# esp8266_lua_test.net
KiCad netlist of a schematic drawn in EAGLE
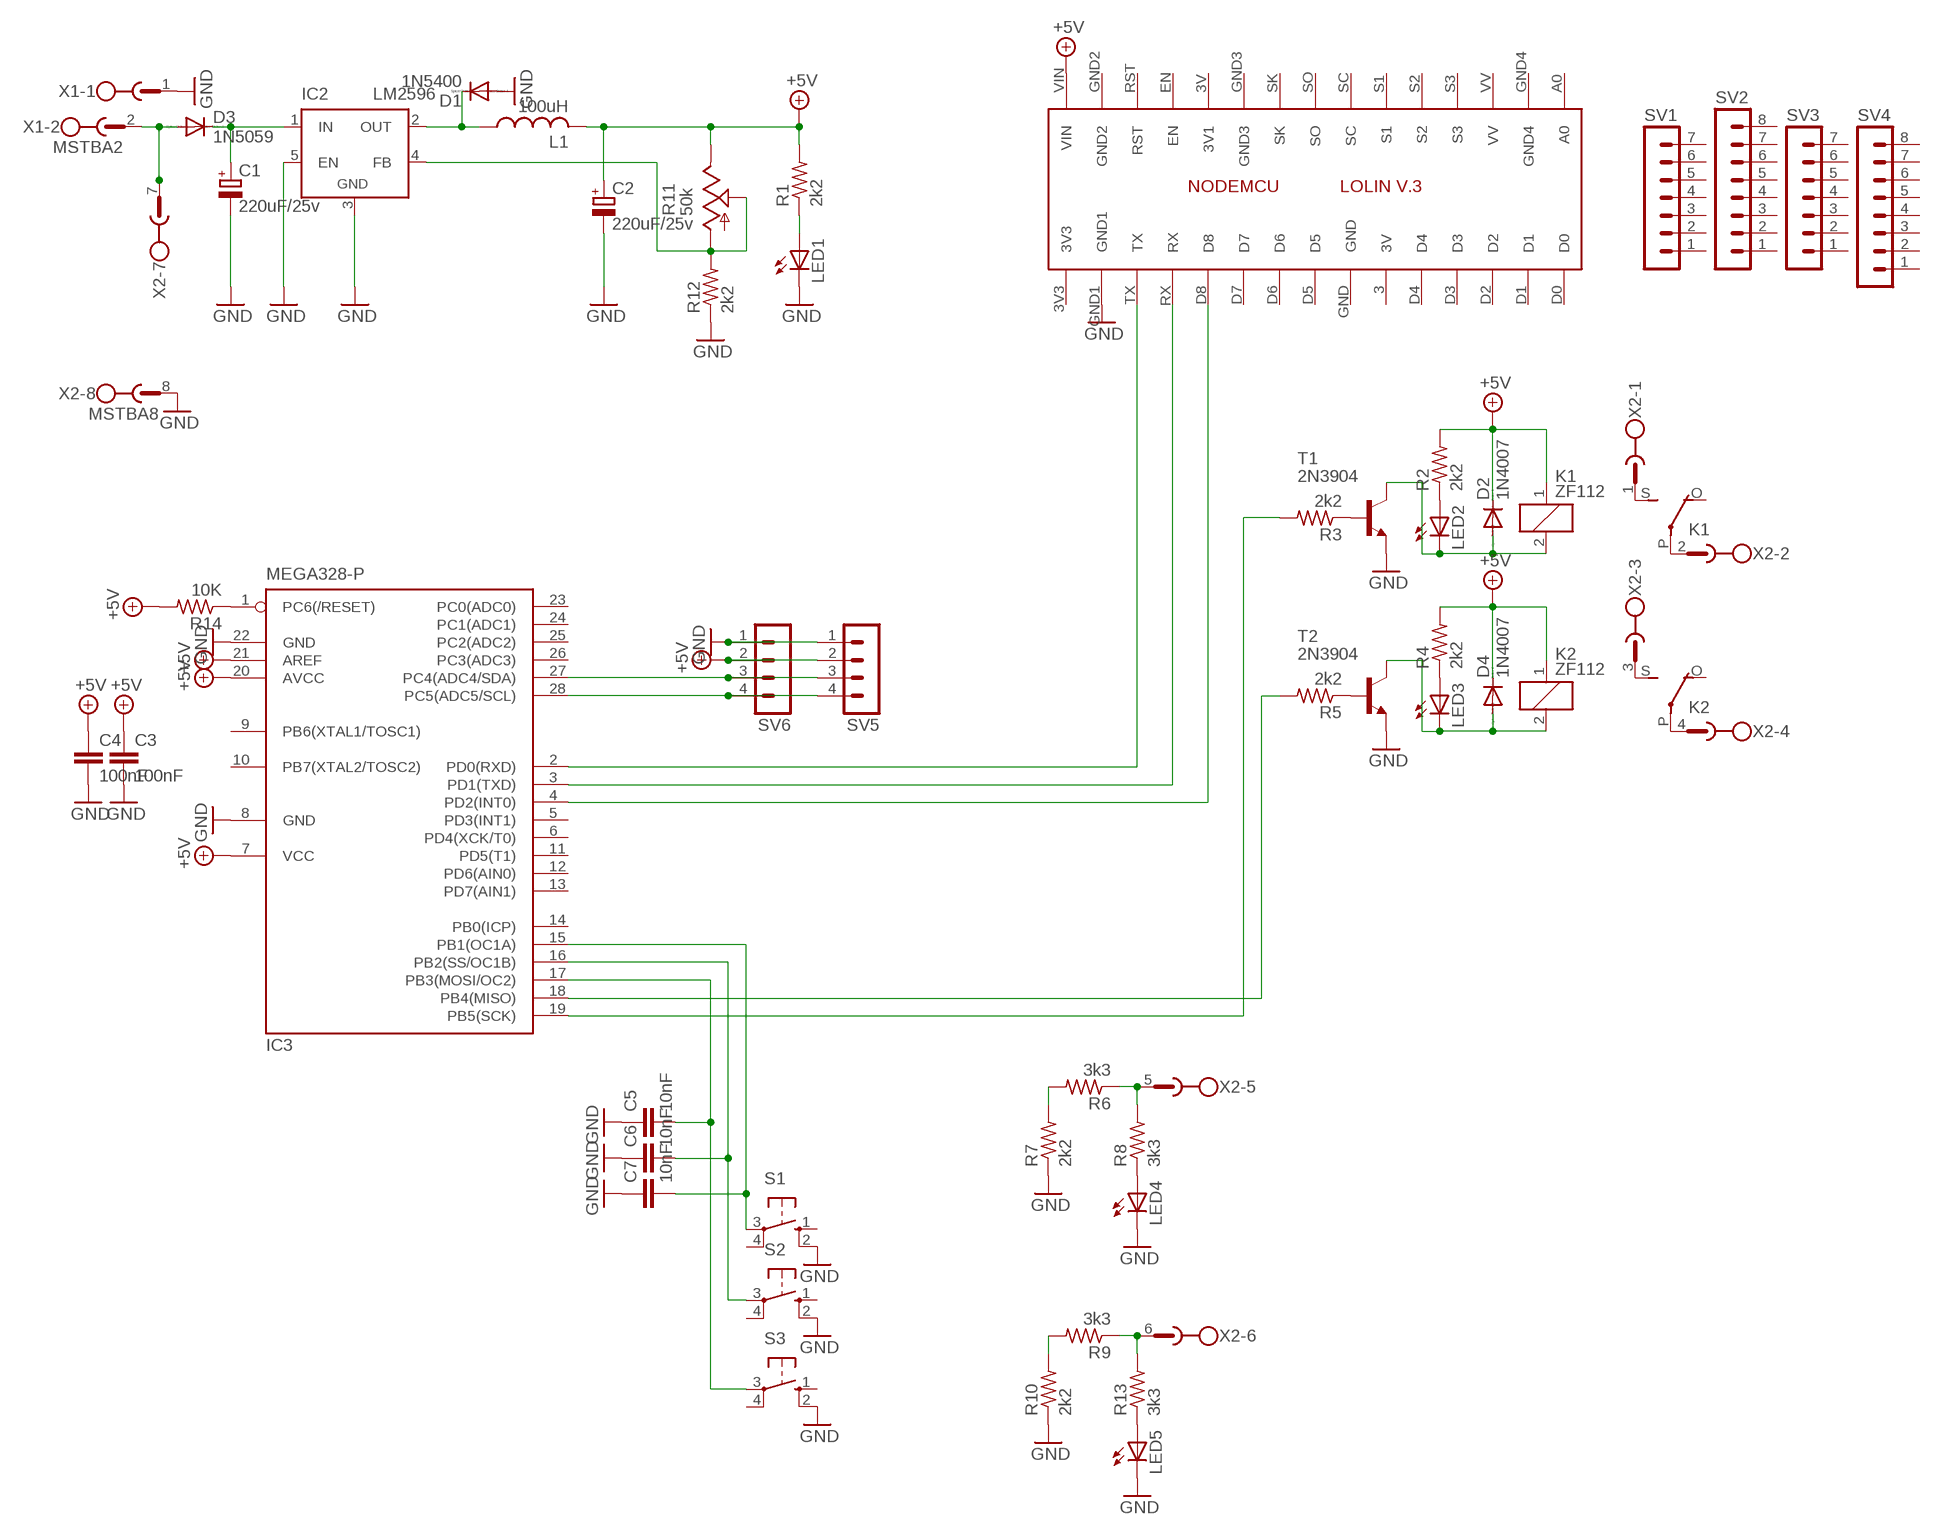
[diagram p0: schematic, sheet 1]

(export (version "E")
  (design (tool "Eeschema 10.0.6"))
  (components
    (comp (ref "C1")
      (value "220uF/25v")
      (footprint "eagle-import:E3,5-10")
      (libsource (lib "eagle-import") (part "CPOL-EUE3.5-10"))
    )
    (comp (ref "C2")
      (value "220uF/25v")
      (footprint "eagle-import:E3,5-10")
      (libsource (lib "eagle-import") (part "CPOL-EUE3.5-10"))
    )
    (comp (ref "C3")
      (value "100nF")
      (footprint "eagle-import:C050-024X044")
      (libsource (lib "eagle-import") (part "C-EU050-024X044"))
    )
    (comp (ref "C4")
      (value "100nF")
      (footprint "eagle-import:C050-024X044")
      (libsource (lib "eagle-import") (part "C-EU050-024X044"))
    )
    (comp (ref "C5")
      (value "10nF")
      (footprint "eagle-import:C050-024X044")
      (libsource (lib "eagle-import") (part "C-EU050-024X044"))
    )
    (comp (ref "C6")
      (value "10nF")
      (footprint "eagle-import:C050-024X044")
      (libsource (lib "eagle-import") (part "C-EU050-024X044"))
    )
    (comp (ref "C7")
      (value "10nF")
      (footprint "eagle-import:C050-024X044")
      (libsource (lib "eagle-import") (part "C-EU050-024X044"))
    )
    (comp (ref "D1")
      (value "1N5400")
      (footprint "eagle-import:DO201-15")
      (libsource (lib "eagle-import") (part "1N5400"))
    )
    (comp (ref "D2")
      (value "1N4007")
      (footprint "eagle-import:DO35-7")
      (libsource (lib "eagle-import") (part "1N4148DO35-7"))
    )
    (comp (ref "D3")
      (value "1N5059")
      (footprint "eagle-import:DO204-10")
      (libsource (lib "eagle-import") (part "1N5059"))
    )
    (comp (ref "D4")
      (value "1N4007")
      (footprint "eagle-import:DO35-7")
      (libsource (lib "eagle-import") (part "1N4148DO35-7"))
    )
    (comp (ref "IC1")
      (value "LOLINV3")
      (footprint "eagle-import:LOLINV3")
      (libsource (lib "eagle-import") (part "LOLINV3"))
    )
    (comp (ref "IC2")
      (value "LM2596")
      (footprint "eagle-import:TO220-51")
      (libsource (lib "eagle-import") (part "LM2596TV"))
    )
    (comp (ref "IC3")
      (value "MEGA328-P")
      (footprint "eagle-import:DIL28-3")
      (libsource (lib "eagle-import") (part "MEGA8-P"))
    )
    (comp (ref "K1")
      (value "ZF112")
      (footprint "eagle-import:ZF112")
      (libsource (lib "eagle-import") (part "ZF112"))
    )
    (comp (ref "K2")
      (value "ZF112")
      (footprint "eagle-import:ZF112")
      (libsource (lib "eagle-import") (part "ZF112"))
    )
    (comp (ref "L1")
      (value "100uH")
      (footprint "eagle-import:6000-XXXX-RC")
      (libsource (lib "eagle-import") (part "L-US6000-XXX-RC"))
    )
    (comp (ref "LED1")
      (value "LED3MM")
      (footprint "eagle-import:LED3MM")
      (libsource (lib "eagle-import") (part "LED3MM"))
    )
    (comp (ref "LED2")
      (value "LED3MM")
      (footprint "eagle-import:LED3MM")
      (libsource (lib "eagle-import") (part "LED3MM"))
    )
    (comp (ref "LED3")
      (value "LED3MM")
      (footprint "eagle-import:LED3MM")
      (libsource (lib "eagle-import") (part "LED3MM"))
    )
    (comp (ref "LED4")
      (value "LED3MM")
      (footprint "eagle-import:LED3MM")
      (libsource (lib "eagle-import") (part "LED3MM"))
    )
    (comp (ref "LED5")
      (value "LED3MM")
      (footprint "eagle-import:LED3MM")
      (libsource (lib "eagle-import") (part "LED3MM"))
    )
    (comp (ref "R1")
      (value "2k2")
      (footprint "eagle-import:0207_10")
      (libsource (lib "eagle-import") (part "R-US_0207/10"))
    )
    (comp (ref "R2")
      (value "2k2")
      (footprint "eagle-import:0207_10")
      (libsource (lib "eagle-import") (part "R-US_0207/10"))
    )
    (comp (ref "R3")
      (value "2k2")
      (footprint "eagle-import:0207_10")
      (libsource (lib "eagle-import") (part "R-US_0207/10"))
    )
    (comp (ref "R4")
      (value "2k2")
      (footprint "eagle-import:0207_10")
      (libsource (lib "eagle-import") (part "R-US_0207/10"))
    )
    (comp (ref "R5")
      (value "2k2")
      (footprint "eagle-import:0207_10")
      (libsource (lib "eagle-import") (part "R-US_0207/10"))
    )
    (comp (ref "R6")
      (value "3k3")
      (footprint "eagle-import:0207_10")
      (libsource (lib "eagle-import") (part "R-US_0207/10"))
    )
    (comp (ref "R7")
      (value "2k2")
      (footprint "eagle-import:0207_10")
      (libsource (lib "eagle-import") (part "R-US_0207/10"))
    )
    (comp (ref "R8")
      (value "3k3")
      (footprint "eagle-import:0207_10")
      (libsource (lib "eagle-import") (part "R-US_0207/10"))
    )
    (comp (ref "R9")
      (value "3k3")
      (footprint "eagle-import:0207_10")
      (libsource (lib "eagle-import") (part "R-US_0207/10"))
    )
    (comp (ref "R10")
      (value "2k2")
      (footprint "eagle-import:0207_10")
      (libsource (lib "eagle-import") (part "R-US_0207/10"))
    )
    (comp (ref "R11")
      (value "50k")
      (footprint "eagle-import:B25P")
      (libsource (lib "eagle-import") (part "TRIM_US-B25P"))
    )
    (comp (ref "R12")
      (value "2k2")
      (footprint "eagle-import:0207_10")
      (libsource (lib "eagle-import") (part "R-US_0207/10"))
    )
    (comp (ref "R13")
      (value "3k3")
      (footprint "eagle-import:0207_10")
      (libsource (lib "eagle-import") (part "R-US_0207/10"))
    )
    (comp (ref "R14")
      (value "10K")
      (footprint "eagle-import:0207_10")
      (libsource (lib "eagle-import") (part "R-US_0207/10"))
    )
    (comp (ref "S1")
      (value "10-XX")
      (footprint "eagle-import:B3F-10XX")
      (fields (field (name "MPN") "B3F-1000"))
      (libsource (lib "eagle-import") (part "10-XX"))
    )
    (comp (ref "S2")
      (value "10-XX")
      (footprint "eagle-import:B3F-10XX")
      (fields (field (name "MPN") "B3F-1000"))
      (libsource (lib "eagle-import") (part "10-XX"))
    )
    (comp (ref "S3")
      (value "10-XX")
      (footprint "eagle-import:B3F-10XX")
      (fields (field (name "MPN") "B3F-1000"))
      (libsource (lib "eagle-import") (part "10-XX"))
    )
    (comp (ref "SV1")
      (value "MA07-1")
      (footprint "eagle-import:MA07-1")
      (libsource (lib "eagle-import") (part "MA07-1"))
    )
    (comp (ref "SV2")
      (value "MA08-1")
      (footprint "eagle-import:MA08-1")
      (libsource (lib "eagle-import") (part "MA08-1"))
    )
    (comp (ref "SV3")
      (value "MA07-1")
      (footprint "eagle-import:MA07-1")
      (libsource (lib "eagle-import") (part "MA07-1"))
    )
    (comp (ref "SV4")
      (value "MA08-1")
      (footprint "eagle-import:MA08-1")
      (libsource (lib "eagle-import") (part "MA08-1"))
    )
    (comp (ref "SV5")
      (value "MA04-1")
      (footprint "eagle-import:MA04-1")
      (libsource (lib "eagle-import") (part "MA04-1"))
    )
    (comp (ref "SV6")
      (value "MA04-1")
      (footprint "eagle-import:MA04-1")
      (libsource (lib "eagle-import") (part "MA04-1"))
    )
    (comp (ref "T1")
      (value "2N3904")
      (footprint "eagle-import:TO92-EBC")
      (libsource (lib "eagle-import") (part "-NPN-TO92-EBC2N3904"))
    )
    (comp (ref "T2")
      (value "2N3904")
      (footprint "eagle-import:TO92-EBC")
      (libsource (lib "eagle-import") (part "-NPN-TO92-EBC2N3904"))
    )
    (comp (ref "X1")
      (value "MSTBA2")
      (footprint "eagle-import:MSTBA2")
      (fields (field (name "MF") "FARNELL") (field (name "MPN") "1757242"))
      (libsource (lib "eagle-import") (part "MSTBA2"))
    )
    (comp (ref "X2")
      (value "MSTBA8")
      (footprint "eagle-import:MSTBA8")
      (fields (field (name "MF") "FARNELL") (field (name "MPN") "1757307"))
      (libsource (lib "eagle-import") (part "MSTBA8"))
    )
  )
  (nets
    (net (code "1") (name "+5V") (class "Default")
      (node (ref "C2") (pin "+") (pinfunction "+_+") (pintype "passive"))
      (node (ref "C3") (pin "1") (pinfunction "1_1") (pintype "passive"))
      (node (ref "C4") (pin "1") (pinfunction "1_1") (pintype "passive"))
      (node (ref "D2") (pin "C") (pinfunction "C_C") (pintype "passive"))
      (node (ref "D4") (pin "C") (pinfunction "C_C") (pintype "passive"))
      (node (ref "IC1") (pin "VIN") (pinfunction "VIN_VIN") (pintype "bidirectional"))
      (node (ref "IC3") (pin "20") (pinfunction "AVCC_20") (pintype "power_in"))
      (node (ref "IC3") (pin "21") (pinfunction "AREF_21") (pintype "passive"))
      (node (ref "IC3") (pin "7") (pinfunction "VCC_7") (pintype "power_in"))
      (node (ref "K1") (pin "1") (pinfunction "1_1") (pintype "passive"))
      (node (ref "K2") (pin "1") (pinfunction "1_1") (pintype "passive"))
      (node (ref "L1") (pin "2") (pinfunction "2_2") (pintype "passive"))
      (node (ref "R1") (pin "2") (pinfunction "2_2") (pintype "passive"))
      (node (ref "R11") (pin "E") (pinfunction "E_E") (pintype "passive"))
      (node (ref "R14") (pin "2") (pinfunction "2_2") (pintype "passive"))
      (node (ref "R2") (pin "2") (pinfunction "2_2") (pintype "passive"))
      (node (ref "R4") (pin "2") (pinfunction "2_2") (pintype "passive"))
      (node (ref "SV5") (pin "2") (pinfunction "2_2") (pintype "passive"))
      (node (ref "SV6") (pin "2") (pinfunction "2_2") (pintype "passive"))
    )
    (net (code "2") (name "GND") (class "Default")
      (node (ref "C1") (pin "-") (pinfunction "-_-") (pintype "passive"))
      (node (ref "C2") (pin "-") (pinfunction "-_-") (pintype "passive"))
      (node (ref "C3") (pin "2") (pinfunction "2_2") (pintype "passive"))
      (node (ref "C4") (pin "2") (pinfunction "2_2") (pintype "passive"))
      (node (ref "C5") (pin "1") (pinfunction "1_1") (pintype "passive"))
      (node (ref "C6") (pin "1") (pinfunction "1_1") (pintype "passive"))
      (node (ref "C7") (pin "1") (pinfunction "1_1") (pintype "passive"))
      (node (ref "D1") (pin "A") (pinfunction "A_A") (pintype "passive"))
      (node (ref "IC1") (pin "GND1") (pinfunction "GND1_GND1") (pintype "bidirectional"))
      (node (ref "IC2") (pin "3") (pinfunction "GND_3") (pintype "power_in"))
      (node (ref "IC2") (pin "5") (pinfunction "EN_5") (pintype "input"))
      (node (ref "IC3") (pin "22") (pinfunction "GND_22") (pintype "power_in"))
      (node (ref "IC3") (pin "8") (pinfunction "GND_8") (pintype "power_in"))
      (node (ref "LED1") (pin "K") (pinfunction "C_K") (pintype "passive"))
      (node (ref "LED4") (pin "K") (pinfunction "C_K") (pintype "passive"))
      (node (ref "LED5") (pin "K") (pinfunction "C_K") (pintype "passive"))
      (node (ref "R10") (pin "1") (pinfunction "1_1") (pintype "passive"))
      (node (ref "R12") (pin "1") (pinfunction "1_1") (pintype "passive"))
      (node (ref "R7") (pin "1") (pinfunction "1_1") (pintype "passive"))
      (node (ref "S1") (pin "2") (pinfunction "S1_2") (pintype "passive"))
      (node (ref "S2") (pin "2") (pinfunction "S1_2") (pintype "passive"))
      (node (ref "S3") (pin "2") (pinfunction "S1_2") (pintype "passive"))
      (node (ref "SV5") (pin "1") (pinfunction "1_1") (pintype "passive"))
      (node (ref "SV6") (pin "1") (pinfunction "1_1") (pintype "passive"))
      (node (ref "T1") (pin "E") (pinfunction "E_E") (pintype "passive"))
      (node (ref "T2") (pin "E") (pinfunction "E_E") (pintype "passive"))
      (node (ref "X1") (pin "1") (pinfunction "1_1") (pintype "passive"))
      (node (ref "X2") (pin "8") (pinfunction "1_8") (pintype "passive"))
    )
    (net (code "3") (name "Net-(IC2-FB)") (class "Default")
      (node (ref "IC2") (pin "4") (pinfunction "FB_4") (pintype "input"))
      (node (ref "R11") (pin "A") (pinfunction "A_A") (pintype "passive"))
      (node (ref "R11") (pin "S") (pinfunction "S_S") (pintype "passive"))
      (node (ref "R12") (pin "2") (pinfunction "2_2") (pintype "passive"))
    )
    (net (code "4") (name "Net-(IC2-IN)") (class "Default")
      (node (ref "C1") (pin "+") (pinfunction "+_+") (pintype "passive"))
      (node (ref "D3") (pin "C") (pinfunction "C_C") (pintype "passive"))
      (node (ref "IC2") (pin "1") (pinfunction "IN_1") (pintype "input"))
    )
    (net (code "5") (name "Net-(IC2-OUT)") (class "Default")
      (node (ref "D1") (pin "C") (pinfunction "C_C") (pintype "passive"))
      (node (ref "IC2") (pin "2") (pinfunction "OUT_2") (pintype "output"))
      (node (ref "L1") (pin "1") (pinfunction "1_1") (pintype "passive"))
    )
    (net (code "6") (name "Net-(IC3-PB1(OC1A))") (class "Default")
      (node (ref "C7") (pin "2") (pinfunction "2_2") (pintype "passive"))
      (node (ref "IC3") (pin "15") (pinfunction "PB1(OC1A)_15") (pintype "bidirectional"))
      (node (ref "S1") (pin "3") (pinfunction "P_3") (pintype "passive"))
    )
    (net (code "7") (name "Net-(IC3-PB2(SS{slash}OC1B))") (class "Default")
      (node (ref "C6") (pin "2") (pinfunction "2_2") (pintype "passive"))
      (node (ref "IC3") (pin "16") (pinfunction "PB2(SS/OC1B)_16") (pintype "bidirectional"))
      (node (ref "S2") (pin "3") (pinfunction "P_3") (pintype "passive"))
    )
    (net (code "8") (name "Net-(IC3-PB3(MOSI{slash}OC2))") (class "Default")
      (node (ref "C5") (pin "2") (pinfunction "2_2") (pintype "passive"))
      (node (ref "IC3") (pin "17") (pinfunction "PB3(MOSI/OC2)_17") (pintype "bidirectional"))
      (node (ref "S3") (pin "3") (pinfunction "P_3") (pintype "passive"))
    )
    (net (code "9") (name "Net-(IC3-PB4(MISO))") (class "Default")
      (node (ref "IC3") (pin "18") (pinfunction "PB4(MISO)_18") (pintype "bidirectional"))
      (node (ref "R5") (pin "2") (pinfunction "2_2") (pintype "passive"))
    )
    (net (code "10") (name "Net-(IC3-PB5(SCK))") (class "Default")
      (node (ref "IC3") (pin "19") (pinfunction "PB5(SCK)_19") (pintype "bidirectional"))
      (node (ref "R3") (pin "2") (pinfunction "2_2") (pintype "passive"))
    )
    (net (code "11") (name "Net-(IC3-PC4(ADC4{slash}SDA))") (class "Default")
      (node (ref "IC3") (pin "27") (pinfunction "PC4(ADC4/SDA)_27") (pintype "bidirectional"))
      (node (ref "SV5") (pin "3") (pinfunction "3_3") (pintype "passive"))
      (node (ref "SV6") (pin "3") (pinfunction "3_3") (pintype "passive"))
    )
    (net (code "12") (name "Net-(IC3-PC5(ADC5{slash}SCL))") (class "Default")
      (node (ref "IC3") (pin "28") (pinfunction "PC5(ADC5/SCL)_28") (pintype "bidirectional"))
      (node (ref "SV5") (pin "4") (pinfunction "4_4") (pintype "passive"))
      (node (ref "SV6") (pin "4") (pinfunction "4_4") (pintype "passive"))
    )
    (net (code "13") (name "Net-(IC3-PC6({slash}RESET))") (class "Default")
      (node (ref "IC3") (pin "1") (pinfunction "PC6(/RESET)_1") (pintype "bidirectional"))
      (node (ref "R14") (pin "1") (pinfunction "1_1") (pintype "passive"))
    )
    (net (code "14") (name "Net-(IC3-PD0(RXD))") (class "Default")
      (node (ref "IC1") (pin "TX") (pinfunction "TX_TX") (pintype "bidirectional"))
      (node (ref "IC3") (pin "2") (pinfunction "PD0(RXD)_2") (pintype "bidirectional"))
    )
    (net (code "15") (name "Net-(IC3-PD1(TXD))") (class "Default")
      (node (ref "IC1") (pin "RX") (pinfunction "RX_RX") (pintype "bidirectional"))
      (node (ref "IC3") (pin "3") (pinfunction "PD1(TXD)_3") (pintype "bidirectional"))
    )
    (net (code "16") (name "Net-(IC3-PD2(INT0))") (class "Default")
      (node (ref "IC1") (pin "D8") (pinfunction "D8_D8") (pintype "bidirectional"))
      (node (ref "IC3") (pin "4") (pinfunction "PD2(INT0)_4") (pintype "bidirectional"))
    )
    (net (code "17") (name "Net-(K1-PadS)") (class "Default")
      (node (ref "K1") (pin "S") (pinfunction "S_S") (pintype "passive"))
      (node (ref "X2") (pin "1") (pinfunction "1_1") (pintype "passive"))
    )
    (net (code "18") (name "Net-(LED1-PadA)") (class "Default")
      (node (ref "LED1") (pin "A") (pinfunction "A_A") (pintype "passive"))
      (node (ref "R1") (pin "1") (pinfunction "1_1") (pintype "passive"))
    )
    (net (code "19") (name "Net-(LED2-C)") (class "Default")
      (node (ref "D2") (pin "A") (pinfunction "A_A") (pintype "passive"))
      (node (ref "K1") (pin "2") (pinfunction "2_2") (pintype "passive"))
      (node (ref "LED2") (pin "K") (pinfunction "C_K") (pintype "passive"))
      (node (ref "T1") (pin "C") (pinfunction "C_C") (pintype "passive"))
    )
    (net (code "20") (name "Net-(LED2-PadA)") (class "Default")
      (node (ref "LED2") (pin "A") (pinfunction "A_A") (pintype "passive"))
      (node (ref "R2") (pin "1") (pinfunction "1_1") (pintype "passive"))
    )
    (net (code "21") (name "Net-(LED3-C)") (class "Default")
      (node (ref "D4") (pin "A") (pinfunction "A_A") (pintype "passive"))
      (node (ref "K2") (pin "2") (pinfunction "2_2") (pintype "passive"))
      (node (ref "LED3") (pin "K") (pinfunction "C_K") (pintype "passive"))
      (node (ref "T2") (pin "C") (pinfunction "C_C") (pintype "passive"))
    )
    (net (code "22") (name "Net-(LED3-PadA)") (class "Default")
      (node (ref "LED3") (pin "A") (pinfunction "A_A") (pintype "passive"))
      (node (ref "R4") (pin "1") (pinfunction "1_1") (pintype "passive"))
    )
    (net (code "23") (name "Net-(LED4-PadA)") (class "Default")
      (node (ref "LED4") (pin "A") (pinfunction "A_A") (pintype "passive"))
      (node (ref "R8") (pin "1") (pinfunction "1_1") (pintype "passive"))
    )
    (net (code "24") (name "Net-(LED5-PadA)") (class "Default")
      (node (ref "LED5") (pin "A") (pinfunction "A_A") (pintype "passive"))
      (node (ref "R13") (pin "1") (pinfunction "1_1") (pintype "passive"))
    )
    (net (code "25") (name "Net-(R3-Pad1)") (class "Default")
      (node (ref "R3") (pin "1") (pinfunction "1_1") (pintype "passive"))
      (node (ref "T1") (pin "B") (pinfunction "B_B") (pintype "passive"))
    )
    (net (code "26") (name "Net-(R5-Pad1)") (class "Default")
      (node (ref "R5") (pin "1") (pinfunction "1_1") (pintype "passive"))
      (node (ref "T2") (pin "B") (pinfunction "B_B") (pintype "passive"))
    )
    (net (code "27") (name "Net-(R6-Pad2)") (class "Default")
      (node (ref "R6") (pin "2") (pinfunction "2_2") (pintype "passive"))
      (node (ref "R7") (pin "2") (pinfunction "2_2") (pintype "passive"))
    )
    (net (code "28") (name "Net-(R10-Pad2)") (class "Default")
      (node (ref "R10") (pin "2") (pinfunction "2_2") (pintype "passive"))
      (node (ref "R9") (pin "2") (pinfunction "2_2") (pintype "passive"))
    )
    (net (code "29") (name "Net-(X1B-1)") (class "Default")
      (node (ref "D3") (pin "A") (pinfunction "A_A") (pintype "passive"))
      (node (ref "X1") (pin "2") (pinfunction "1_2") (pintype "passive"))
      (node (ref "X2") (pin "7") (pinfunction "1_7") (pintype "passive"))
    )
    (net (code "30") (name "Net-(X2B-1)") (class "Default")
      (node (ref "K1") (pin "P") (pinfunction "P_P") (pintype "passive"))
      (node (ref "X2") (pin "2") (pinfunction "1_2") (pintype "passive"))
    )
    (net (code "31") (name "Net-(X2C-1)") (class "Default")
      (node (ref "K2") (pin "S") (pinfunction "S_S") (pintype "passive"))
      (node (ref "X2") (pin "3") (pinfunction "1_3") (pintype "passive"))
    )
    (net (code "32") (name "Net-(X2D-1)") (class "Default")
      (node (ref "K2") (pin "P") (pinfunction "P_P") (pintype "passive"))
      (node (ref "X2") (pin "4") (pinfunction "1_4") (pintype "passive"))
    )
    (net (code "33") (name "Net-(X2E-1)") (class "Default")
      (node (ref "R6") (pin "1") (pinfunction "1_1") (pintype "passive"))
      (node (ref "R8") (pin "2") (pinfunction "2_2") (pintype "passive"))
      (node (ref "X2") (pin "5") (pinfunction "1_5") (pintype "passive"))
    )
    (net (code "34") (name "Net-(X2F-1)") (class "Default")
      (node (ref "R13") (pin "2") (pinfunction "2_2") (pintype "passive"))
      (node (ref "R9") (pin "1") (pinfunction "1_1") (pintype "passive"))
      (node (ref "X2") (pin "6") (pinfunction "1_6") (pintype "passive"))
    )
    (net (code "35") (name "unconnected-(IC1-3V-Pad3)") (class "Default")
      (node (ref "IC1") (pin "3") (pinfunction "3V_3") (pintype "bidirectional"))
    )
    (net (code "36") (name "unconnected-(IC1-3V1-Pad3V)") (class "Default")
      (node (ref "IC1") (pin "3V") (pinfunction "3V1_3V") (pintype "bidirectional"))
    )
    (net (code "37") (name "unconnected-(IC1-Pad3V3)") (class "Default")
      (node (ref "IC1") (pin "3V3") (pinfunction "3V3_3V3") (pintype "bidirectional"))
    )
    (net (code "38") (name "unconnected-(IC1-PadA0)") (class "Default")
      (node (ref "IC1") (pin "A0") (pinfunction "A0_A0") (pintype "bidirectional"))
    )
    (net (code "39") (name "unconnected-(IC1-PadD0)") (class "Default")
      (node (ref "IC1") (pin "D0") (pinfunction "D0_D0") (pintype "bidirectional"))
    )
    (net (code "40") (name "unconnected-(IC1-PadD1)") (class "Default")
      (node (ref "IC1") (pin "D1") (pinfunction "D1_D1") (pintype "bidirectional"))
    )
    (net (code "41") (name "unconnected-(IC1-PadD2)") (class "Default")
      (node (ref "IC1") (pin "D2") (pinfunction "D2_D2") (pintype "bidirectional"))
    )
    (net (code "42") (name "unconnected-(IC1-PadD3)") (class "Default")
      (node (ref "IC1") (pin "D3") (pinfunction "D3_D3") (pintype "bidirectional"))
    )
    (net (code "43") (name "unconnected-(IC1-PadD4)") (class "Default")
      (node (ref "IC1") (pin "D4") (pinfunction "D4_D4") (pintype "bidirectional"))
    )
    (net (code "44") (name "unconnected-(IC1-PadD5)") (class "Default")
      (node (ref "IC1") (pin "D5") (pinfunction "D5_D5") (pintype "bidirectional"))
    )
    (net (code "45") (name "unconnected-(IC1-PadD6)") (class "Default")
      (node (ref "IC1") (pin "D6") (pinfunction "D6_D6") (pintype "bidirectional"))
    )
    (net (code "46") (name "unconnected-(IC1-PadD7)") (class "Default")
      (node (ref "IC1") (pin "D7") (pinfunction "D7_D7") (pintype "bidirectional"))
    )
    (net (code "47") (name "unconnected-(IC1-PadEN)") (class "Default")
      (node (ref "IC1") (pin "EN") (pinfunction "EN_EN") (pintype "bidirectional"))
    )
    (net (code "48") (name "unconnected-(IC1-PadGND)") (class "Default")
      (node (ref "IC1") (pin "GND") (pinfunction "GND_GND") (pintype "bidirectional"))
    )
    (net (code "49") (name "unconnected-(IC1-PadGND2)") (class "Default")
      (node (ref "IC1") (pin "GND2") (pinfunction "GND2_GND2") (pintype "bidirectional"))
    )
    (net (code "50") (name "unconnected-(IC1-PadGND3)") (class "Default")
      (node (ref "IC1") (pin "GND3") (pinfunction "GND3_GND3") (pintype "bidirectional"))
    )
    (net (code "51") (name "unconnected-(IC1-PadGND4)") (class "Default")
      (node (ref "IC1") (pin "GND4") (pinfunction "GND4_GND4") (pintype "bidirectional"))
    )
    (net (code "52") (name "unconnected-(IC1-PadRST)") (class "Default")
      (node (ref "IC1") (pin "RST") (pinfunction "RST_RST") (pintype "bidirectional"))
    )
    (net (code "53") (name "unconnected-(IC1-PadS1)") (class "Default")
      (node (ref "IC1") (pin "S1") (pinfunction "S1_S1") (pintype "bidirectional"))
    )
    (net (code "54") (name "unconnected-(IC1-PadS2)") (class "Default")
      (node (ref "IC1") (pin "S2") (pinfunction "S2_S2") (pintype "bidirectional"))
    )
    (net (code "55") (name "unconnected-(IC1-PadS3)") (class "Default")
      (node (ref "IC1") (pin "S3") (pinfunction "S3_S3") (pintype "bidirectional"))
    )
    (net (code "56") (name "unconnected-(IC1-PadSC)") (class "Default")
      (node (ref "IC1") (pin "SC") (pinfunction "SC_SC") (pintype "bidirectional"))
    )
    (net (code "57") (name "unconnected-(IC1-PadSK)") (class "Default")
      (node (ref "IC1") (pin "SK") (pinfunction "SK_SK") (pintype "bidirectional"))
    )
    (net (code "58") (name "unconnected-(IC1-PadSO)") (class "Default")
      (node (ref "IC1") (pin "SO") (pinfunction "SO_SO") (pintype "bidirectional"))
    )
    (net (code "59") (name "unconnected-(IC1-PadVV)") (class "Default")
      (node (ref "IC1") (pin "VV") (pinfunction "VV_VV") (pintype "bidirectional"))
    )
    (net (code "60") (name "unconnected-(IC3-PB0(ICP)-Pad14)") (class "Default")
      (node (ref "IC3") (pin "14") (pinfunction "PB0(ICP)_14") (pintype "bidirectional"))
    )
    (net (code "61") (name "unconnected-(IC3-PB6(XTAL1{slash}TOSC1)-Pad9)") (class "Default")
      (node (ref "IC3") (pin "9") (pinfunction "PB6(XTAL1/TOSC1)_9") (pintype "bidirectional"))
    )
    (net (code "62") (name "unconnected-(IC3-PB7(XTAL2{slash}TOSC2)-Pad10)") (class "Default")
      (node (ref "IC3") (pin "10") (pinfunction "PB7(XTAL2/TOSC2)_10") (pintype "bidirectional"))
    )
    (net (code "63") (name "unconnected-(IC3-PC0(ADC0)-Pad23)") (class "Default")
      (node (ref "IC3") (pin "23") (pinfunction "PC0(ADC0)_23") (pintype "bidirectional"))
    )
    (net (code "64") (name "unconnected-(IC3-PC1(ADC1)-Pad24)") (class "Default")
      (node (ref "IC3") (pin "24") (pinfunction "PC1(ADC1)_24") (pintype "bidirectional"))
    )
    (net (code "65") (name "unconnected-(IC3-PC2(ADC2)-Pad25)") (class "Default")
      (node (ref "IC3") (pin "25") (pinfunction "PC2(ADC2)_25") (pintype "bidirectional"))
    )
    (net (code "66") (name "unconnected-(IC3-PC3(ADC3)-Pad26)") (class "Default")
      (node (ref "IC3") (pin "26") (pinfunction "PC3(ADC3)_26") (pintype "bidirectional"))
    )
    (net (code "67") (name "unconnected-(IC3-PD3(INT1)-Pad5)") (class "Default")
      (node (ref "IC3") (pin "5") (pinfunction "PD3(INT1)_5") (pintype "bidirectional"))
    )
    (net (code "68") (name "unconnected-(IC3-PD4(XCK{slash}T0)-Pad6)") (class "Default")
      (node (ref "IC3") (pin "6") (pinfunction "PD4(XCK/T0)_6") (pintype "bidirectional"))
    )
    (net (code "69") (name "unconnected-(IC3-PD5(T1)-Pad11)") (class "Default")
      (node (ref "IC3") (pin "11") (pinfunction "PD5(T1)_11") (pintype "bidirectional"))
    )
    (net (code "70") (name "unconnected-(IC3-PD6(AIN0)-Pad12)") (class "Default")
      (node (ref "IC3") (pin "12") (pinfunction "PD6(AIN0)_12") (pintype "bidirectional"))
    )
    (net (code "71") (name "unconnected-(IC3-PD7(AIN1)-Pad13)") (class "Default")
      (node (ref "IC3") (pin "13") (pinfunction "PD7(AIN1)_13") (pintype "bidirectional"))
    )
    (net (code "72") (name "unconnected-(K1-PadO)") (class "Default")
      (node (ref "K1") (pin "O") (pinfunction "O_O") (pintype "passive"))
    )
    (net (code "73") (name "unconnected-(K2-PadO)") (class "Default")
      (node (ref "K2") (pin "O") (pinfunction "O_O") (pintype "passive"))
    )
    (net (code "74") (name "unconnected-(S1-P1-Pad4)") (class "Default")
      (node (ref "S1") (pin "4") (pinfunction "P1_4") (pintype "passive"))
    )
    (net (code "75") (name "unconnected-(S1-S-Pad1)") (class "Default")
      (node (ref "S1") (pin "1") (pinfunction "S_1") (pintype "passive"))
    )
    (net (code "76") (name "unconnected-(S2-P1-Pad4)") (class "Default")
      (node (ref "S2") (pin "4") (pinfunction "P1_4") (pintype "passive"))
    )
    (net (code "77") (name "unconnected-(S2-S-Pad1)") (class "Default")
      (node (ref "S2") (pin "1") (pinfunction "S_1") (pintype "passive"))
    )
    (net (code "78") (name "unconnected-(S3-P1-Pad4)") (class "Default")
      (node (ref "S3") (pin "4") (pinfunction "P1_4") (pintype "passive"))
    )
    (net (code "79") (name "unconnected-(S3-S-Pad1)") (class "Default")
      (node (ref "S3") (pin "1") (pinfunction "S_1") (pintype "passive"))
    )
    (net (code "80") (name "unconnected-(SV1-Pad1)") (class "Default")
      (node (ref "SV1") (pin "1") (pinfunction "1_1") (pintype "passive"))
    )
    (net (code "81") (name "unconnected-(SV1-Pad2)") (class "Default")
      (node (ref "SV1") (pin "2") (pinfunction "2_2") (pintype "passive"))
    )
    (net (code "82") (name "unconnected-(SV1-Pad3)") (class "Default")
      (node (ref "SV1") (pin "3") (pinfunction "3_3") (pintype "passive"))
    )
    (net (code "83") (name "unconnected-(SV1-Pad4)") (class "Default")
      (node (ref "SV1") (pin "4") (pinfunction "4_4") (pintype "passive"))
    )
    (net (code "84") (name "unconnected-(SV1-Pad5)") (class "Default")
      (node (ref "SV1") (pin "5") (pinfunction "5_5") (pintype "passive"))
    )
    (net (code "85") (name "unconnected-(SV1-Pad6)") (class "Default")
      (node (ref "SV1") (pin "6") (pinfunction "6_6") (pintype "passive"))
    )
    (net (code "86") (name "unconnected-(SV1-Pad7)") (class "Default")
      (node (ref "SV1") (pin "7") (pinfunction "7_7") (pintype "passive"))
    )
    (net (code "87") (name "unconnected-(SV2-Pad1)") (class "Default")
      (node (ref "SV2") (pin "1") (pinfunction "1_1") (pintype "passive"))
    )
    (net (code "88") (name "unconnected-(SV2-Pad2)") (class "Default")
      (node (ref "SV2") (pin "2") (pinfunction "2_2") (pintype "passive"))
    )
    (net (code "89") (name "unconnected-(SV2-Pad3)") (class "Default")
      (node (ref "SV2") (pin "3") (pinfunction "3_3") (pintype "passive"))
    )
    (net (code "90") (name "unconnected-(SV2-Pad4)") (class "Default")
      (node (ref "SV2") (pin "4") (pinfunction "4_4") (pintype "passive"))
    )
    (net (code "91") (name "unconnected-(SV2-Pad5)") (class "Default")
      (node (ref "SV2") (pin "5") (pinfunction "5_5") (pintype "passive"))
    )
    (net (code "92") (name "unconnected-(SV2-Pad6)") (class "Default")
      (node (ref "SV2") (pin "6") (pinfunction "6_6") (pintype "passive"))
    )
    (net (code "93") (name "unconnected-(SV2-Pad7)") (class "Default")
      (node (ref "SV2") (pin "7") (pinfunction "7_7") (pintype "passive"))
    )
    (net (code "94") (name "unconnected-(SV2-Pad8)") (class "Default")
      (node (ref "SV2") (pin "8") (pinfunction "8_8") (pintype "passive"))
    )
    (net (code "95") (name "unconnected-(SV3-Pad1)") (class "Default")
      (node (ref "SV3") (pin "1") (pinfunction "1_1") (pintype "passive"))
    )
    (net (code "96") (name "unconnected-(SV3-Pad2)") (class "Default")
      (node (ref "SV3") (pin "2") (pinfunction "2_2") (pintype "passive"))
    )
    (net (code "97") (name "unconnected-(SV3-Pad3)") (class "Default")
      (node (ref "SV3") (pin "3") (pinfunction "3_3") (pintype "passive"))
    )
    (net (code "98") (name "unconnected-(SV3-Pad4)") (class "Default")
      (node (ref "SV3") (pin "4") (pinfunction "4_4") (pintype "passive"))
    )
    (net (code "99") (name "unconnected-(SV3-Pad5)") (class "Default")
      (node (ref "SV3") (pin "5") (pinfunction "5_5") (pintype "passive"))
    )
    (net (code "100") (name "unconnected-(SV3-Pad6)") (class "Default")
      (node (ref "SV3") (pin "6") (pinfunction "6_6") (pintype "passive"))
    )
    (net (code "101") (name "unconnected-(SV3-Pad7)") (class "Default")
      (node (ref "SV3") (pin "7") (pinfunction "7_7") (pintype "passive"))
    )
    (net (code "102") (name "unconnected-(SV4-Pad1)") (class "Default")
      (node (ref "SV4") (pin "1") (pinfunction "1_1") (pintype "passive"))
    )
    (net (code "103") (name "unconnected-(SV4-Pad2)") (class "Default")
      (node (ref "SV4") (pin "2") (pinfunction "2_2") (pintype "passive"))
    )
    (net (code "104") (name "unconnected-(SV4-Pad3)") (class "Default")
      (node (ref "SV4") (pin "3") (pinfunction "3_3") (pintype "passive"))
    )
    (net (code "105") (name "unconnected-(SV4-Pad4)") (class "Default")
      (node (ref "SV4") (pin "4") (pinfunction "4_4") (pintype "passive"))
    )
    (net (code "106") (name "unconnected-(SV4-Pad5)") (class "Default")
      (node (ref "SV4") (pin "5") (pinfunction "5_5") (pintype "passive"))
    )
    (net (code "107") (name "unconnected-(SV4-Pad6)") (class "Default")
      (node (ref "SV4") (pin "6") (pinfunction "6_6") (pintype "passive"))
    )
    (net (code "108") (name "unconnected-(SV4-Pad7)") (class "Default")
      (node (ref "SV4") (pin "7") (pinfunction "7_7") (pintype "passive"))
    )
    (net (code "109") (name "unconnected-(SV4-Pad8)") (class "Default")
      (node (ref "SV4") (pin "8") (pinfunction "8_8") (pintype "passive"))
    )
  )
)
